# Schematic.net
KiCad netlist of a schematic drawn in Altium Designer
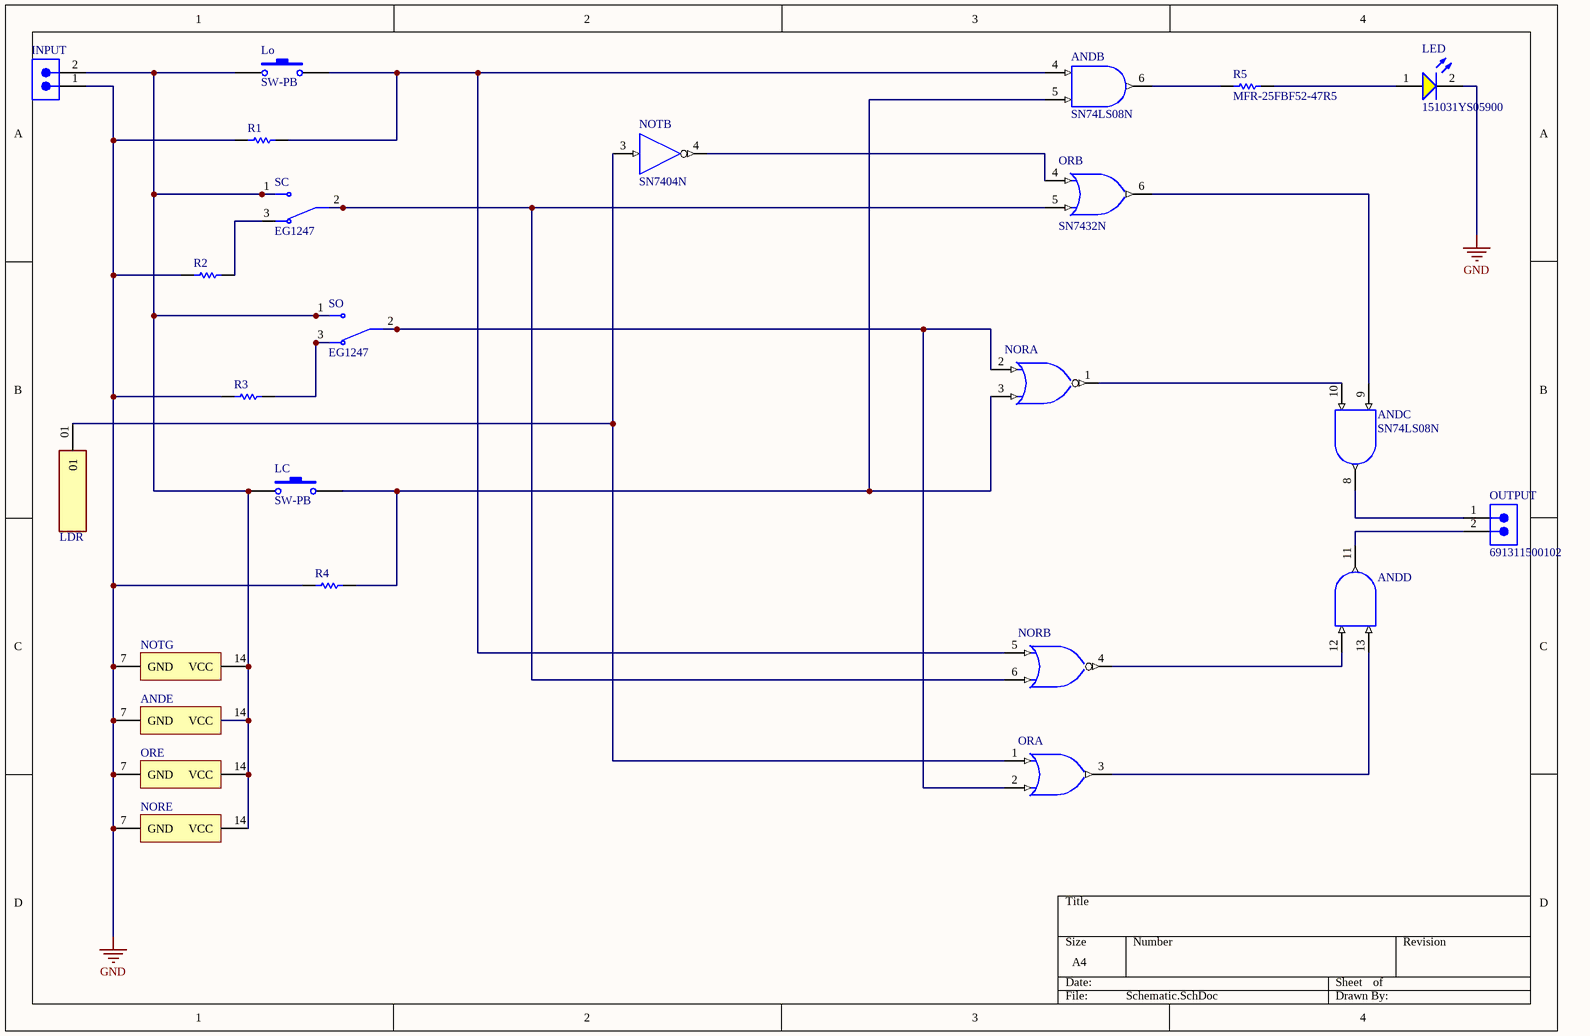
[diagram p0: Schematic.SchDoc]

(export (version "E")
  (design (tool "Eeschema 10.0.6"))
  (components
    (comp (ref "AND")
      (value "SN74LS08N")
      (footprint "N0014A")
      (description "Quadruple 2-Input Positive-AND Gates, N0014A, TUBE")
      (fields
        (field (name "MANUFACTURER") "Texas Instruments")
        (field (name "GENERIC PART NUMBER") "SN74LS08")
      )
      (libsource (lib "") (part "TI-AND-4-2IN-14_2"))
    )
    (comp (ref "INPUT")
      (value "~")
      (footprint "691311500102")
      (fields (field (name "VOLTAGE") "300V"))
      (libsource (lib "Altium Content Vault") (part "TBL - 1R - 02P - Male"))
    )
    (comp (ref "LC")
      (value "SW-PB")
      (footprint "SPST-2")
      (description "Switch")
      (fields (field (name "PUBLISHER") "Altium Limited"))
      (libsource (lib "Miscellaneous Devices") (part "SW-PB"))
    )
    (comp (ref "LDR")
      (value "~")
      (footprint "SAMTEC_HTSW-101-06-T-S")
      (fields (field (name "MP") "HTSW-101-06-T-S"))
      (libsource (lib "HTSW-101-06-T-S") (part "HTSW-101-06-T-S"))
    )
    (comp (ref "LED")
      (value "151031YS05900")
      (footprint "WL-TMRC_D3.95H5.3")
      (libsource (lib "Altium Content Vault") (part "LED_Yellow_1A-2K"))
    )
    (comp (ref "Lo")
      (value "SW-PB")
      (footprint "SPST-2")
      (description "Switch")
      (fields (field (name "PUBLISHER") "Altium Limited"))
      (libsource (lib "Miscellaneous Devices") (part "SW-PB"))
    )
    (comp (ref "NOR")
      (value "~")
      (footprint "N0014A")
      (description "Quad 2-input Positive-NOR gates, N0014A, TUBE")
      (fields (field (name "GENERIC PART NUMBER") "SN7402") (field (name "MANUFACTURER") "Texas Instruments"))
      (libsource (lib "Altium Content Vault") (part "TI-NOR-4-2IN-14"))
    )
    (comp (ref "NOT")
      (value "SN7404N")
      (footprint "N0014A")
      (description "Hex inverters, N0014A, TUBE")
      (fields (field (name "GENERIC PART NUMBER") "SN7404") (field (name "MANUFACTURER") "Texas Instruments"))
      (libsource (lib "Altium Content Vault") (part "TI-CD_SNX4XXXXXX4X_19A-14"))
    )
    (comp (ref "OR")
      (value "SN7432N")
      (footprint "N0014A")
      (description "Quad 2-input positive-OR gates, N0014A, TUBE")
      (fields (field (name "MANUFACTURER") "Texas Instruments") (field (name "GENERIC PART NUMBER") "SN7432"))
      (libsource (lib "Altium Content Vault") (part "TI-OR-4-2IN-14"))
    )
    (comp (ref "OUTPUT")
      (value "691311500102")
      (footprint "691311500102")
      (fields (field (name "VOLTAGE") "300V"))
      (libsource (lib "Altium Content Vault") (part "TBL - 1R - 02P - Male"))
    )
    (comp (ref "R1")
      (value "~")
      (footprint "RESA60-630X240")
      (description "Axial Resistor, 47.5 Ohm, +/- 1%, 0.25 W, -55 to 155 degC, 2-Pin THD, RoHS, Bulk")
      (libsource (lib "Altium Content Vault") (part "RES-2"))
    )
    (comp (ref "R2")
      (value "~")
      (footprint "RESA60-630X240")
      (description "Axial Resistor, 47.5 Ohm, +/- 1%, 0.25 W, -55 to 155 degC, 2-Pin THD, RoHS, Bulk")
      (libsource (lib "Altium Content Vault") (part "RES-2"))
    )
    (comp (ref "R3")
      (value "~")
      (footprint "RESA60-630X240")
      (description "Axial Resistor, 47.5 Ohm, +/- 1%, 0.25 W, -55 to 155 degC, 2-Pin THD, RoHS, Bulk")
      (libsource (lib "Altium Content Vault") (part "RES-2"))
    )
    (comp (ref "R4")
      (value "~")
      (footprint "RESA60-630X240")
      (description "Axial Resistor, 47.5 Ohm, +/- 1%, 0.25 W, -55 to 155 degC, 2-Pin THD, RoHS, Bulk")
      (libsource (lib "Altium Content Vault") (part "RES-2"))
    )
    (comp (ref "R5")
      (value "MFR-25FBF52-47R5")
      (footprint "RESA60-630X240")
      (description "Axial Resistor, 47.5 Ohm, +/- 1%, 0.25 W, -55 to 155 degC, 2-Pin THD, RoHS, Bulk")
      (libsource (lib "Altium Content Vault") (part "RES-2"))
    )
    (comp (ref "SC")
      (value "EG1247")
      (footprint "SW_EG1247")
      (description "Slide Switch SPDT Through Hole, Right Angle")
      (fields (field (name "MF") "E-Switch"))
      (libsource (lib "EG1247 (1)") (part "EG1247"))
    )
    (comp (ref "SO")
      (value "EG1247")
      (footprint "SW_EG1247")
      (description "Slide Switch SPDT Through Hole, Right Angle")
      (fields (field (name "MF") "E-Switch"))
      (libsource (lib "EG1247 (1)") (part "EG1247"))
    )
  )
  (nets
    (net (code "1") (name "GND") (class "Default")
      (node (ref "AND") (pin "7") (pinfunction "GND_7") (pintype "power_in"))
      (node (ref "INPUT") (pin "1") (pinfunction "1_1") (pintype "passive"))
      (node (ref "LED") (pin "2") (pinfunction "K_2") (pintype "passive"))
      (node (ref "NOR") (pin "7") (pinfunction "GND_7") (pintype "power_in"))
      (node (ref "NOT") (pin "7") (pinfunction "GND_7") (pintype "power_in"))
      (node (ref "OR") (pin "7") (pinfunction "GND_7") (pintype "power_in"))
      (node (ref "R1") (pin "1") (pinfunction "1_1") (pintype "passive"))
      (node (ref "R2") (pin "1") (pinfunction "1_1") (pintype "passive"))
      (node (ref "R3") (pin "1") (pinfunction "1_1") (pintype "passive"))
      (node (ref "R4") (pin "1") (pinfunction "1_1") (pintype "passive"))
    )
    (net (code "2") (name "Net-(ANDB-2A)") (class "Default")
      (node (ref "AND") (pin "4") (pinfunction "2A_4") (pintype "input"))
      (node (ref "Lo") (pin "2") (pinfunction "2_2") (pintype "passive"))
      (node (ref "NOR") (pin "5") (pinfunction "2A_5") (pintype "input"))
      (node (ref "R1") (pin "2") (pinfunction "2_2") (pintype "passive"))
    )
    (net (code "3") (name "Net-(ANDB-2B)") (class "Default")
      (node (ref "AND") (pin "5") (pinfunction "2B_5") (pintype "input"))
      (node (ref "LC") (pin "2") (pinfunction "2_2") (pintype "passive"))
      (node (ref "NOR") (pin "3") (pinfunction "1B_3") (pintype "input"))
      (node (ref "R4") (pin "2") (pinfunction "2_2") (pintype "passive"))
    )
    (net (code "4") (name "Net-(ANDB-2Y)") (class "Default")
      (node (ref "AND") (pin "6") (pinfunction "2Y_6") (pintype "output"))
      (node (ref "R5") (pin "1") (pinfunction "1_1") (pintype "passive"))
    )
    (net (code "5") (name "Net-(ANDC-3A)") (class "Default")
      (node (ref "AND") (pin "9") (pinfunction "3A_9") (pintype "input"))
      (node (ref "OR") (pin "6") (pinfunction "2Y_6") (pintype "output"))
    )
    (net (code "6") (name "Net-(ANDC-3B)") (class "Default")
      (node (ref "AND") (pin "10") (pinfunction "3B_10") (pintype "input"))
      (node (ref "NOR") (pin "1") (pinfunction "1Y_1") (pintype "output"))
    )
    (net (code "7") (name "Net-(ANDC-3Y)") (class "Default")
      (node (ref "AND") (pin "8") (pinfunction "3Y_8") (pintype "output"))
      (node (ref "OUTPUT") (pin "1") (pinfunction "1_1") (pintype "passive"))
    )
    (net (code "8") (name "Net-(ANDD-4A)") (class "Default")
      (node (ref "AND") (pin "12") (pinfunction "4A_12") (pintype "input"))
      (node (ref "NOR") (pin "4") (pinfunction "2Y_4") (pintype "output"))
    )
    (net (code "9") (name "Net-(ANDD-4B)") (class "Default")
      (node (ref "AND") (pin "13") (pinfunction "4B_13") (pintype "input"))
      (node (ref "OR") (pin "3") (pinfunction "1Y_3") (pintype "output"))
    )
    (net (code "10") (name "Net-(ANDD-4Y)") (class "Default")
      (node (ref "AND") (pin "11") (pinfunction "4Y_11") (pintype "output"))
      (node (ref "OUTPUT") (pin "2") (pinfunction "2_2") (pintype "passive"))
    )
    (net (code "11") (name "Net-(ANDE-VCC)") (class "Default")
      (node (ref "AND") (pin "14") (pinfunction "VCC_14") (pintype "power_in"))
      (node (ref "INPUT") (pin "2") (pinfunction "2_2") (pintype "passive"))
      (node (ref "LC") (pin "1") (pinfunction "1_1") (pintype "passive"))
      (node (ref "Lo") (pin "1") (pinfunction "1_1") (pintype "passive"))
      (node (ref "NOR") (pin "14") (pinfunction "VCC_14") (pintype "power_in"))
      (node (ref "NOT") (pin "14") (pinfunction "VCC_14") (pintype "power_in"))
      (node (ref "OR") (pin "14") (pinfunction "VCC_14") (pintype "power_in"))
      (node (ref "SC") (pin "1") (pinfunction "1_1") (pintype "passive"))
      (node (ref "SO") (pin "1") (pinfunction "1_1") (pintype "passive"))
    )
    (net (code "12") (name "Net-(LED-A)") (class "Default")
      (node (ref "LED") (pin "1") (pinfunction "A_1") (pintype "passive"))
      (node (ref "R5") (pin "2") (pinfunction "2_2") (pintype "passive"))
    )
    (net (code "13") (name "Net-(NORA-1A)") (class "Default")
      (node (ref "NOR") (pin "2") (pinfunction "1A_2") (pintype "input"))
      (node (ref "OR") (pin "2") (pinfunction "1B_2") (pintype "input"))
      (node (ref "SO") (pin "2") (pinfunction "2_2") (pintype "passive"))
    )
    (net (code "14") (name "Net-(NORB-2B)") (class "Default")
      (node (ref "NOR") (pin "6") (pinfunction "2B_6") (pintype "input"))
      (node (ref "OR") (pin "5") (pinfunction "2B_5") (pintype "input"))
      (node (ref "SC") (pin "2") (pinfunction "2_2") (pintype "passive"))
    )
    (net (code "15") (name "Net-(NOTB-2A)") (class "Default")
      (node (ref "LDR") (pin "01") (pinfunction "01_01") (pintype "passive"))
      (node (ref "NOT") (pin "3") (pinfunction "2A_3") (pintype "input"))
      (node (ref "OR") (pin "1") (pinfunction "1A_1") (pintype "input"))
    )
    (net (code "16") (name "Net-(NOTB-~{2Y})") (class "Default")
      (node (ref "NOT") (pin "4") (pinfunction "~{2Y}_4") (pintype "output"))
      (node (ref "OR") (pin "4") (pinfunction "2A_4") (pintype "input"))
    )
    (net (code "17") (name "Net-(R2-Pad2)") (class "Default")
      (node (ref "R2") (pin "2") (pinfunction "2_2") (pintype "passive"))
      (node (ref "SC") (pin "3") (pinfunction "3_3") (pintype "passive"))
    )
    (net (code "18") (name "Net-(R3-Pad2)") (class "Default")
      (node (ref "R3") (pin "2") (pinfunction "2_2") (pintype "passive"))
      (node (ref "SO") (pin "3") (pinfunction "3_3") (pintype "passive"))
    )
  )
)
